# 5V_Block.net
KiCad netlist of a schematic drawn in Altium Designer
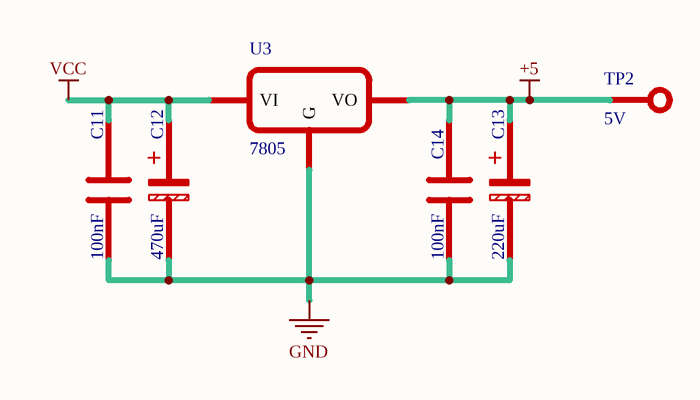
[diagram p0: 5V_Block.SchDoc]

(export (version "E")
  (design (tool "Eeschema 10.0.6"))
  (components
    (comp (ref "C11")
      (value "100nF")
      (footprint "C0805")
      (description "Ceramic Capacitor")
      (libsource (lib "CTAI-Library") (part "CAP-CER"))
    )
    (comp (ref "C12")
      (value "470uF")
      (footprint "CAP-AL-4x5.4")
      (description "Aluminum Capacitor")
      (libsource (lib "CTAI-Library") (part "CAP-ALU"))
    )
    (comp (ref "C13")
      (value "220uF")
      (footprint "CAP-AL-4x5.4")
      (description "Aluminum Capacitor")
      (libsource (lib "CTAI-Library") (part "CAP-ALU"))
    )
    (comp (ref "C14")
      (value "100nF")
      (footprint "C0805")
      (description "Ceramic Capacitor")
      (libsource (lib "CTAI-Library") (part "CAP-CER"))
    )
    (comp (ref "TP2")
      (value "5V")
      (footprint "Test Point")
      (description "Test Point")
      (libsource (lib "CTAI-Library") (part "TestPoint"))
    )
    (comp (ref "U3")
      (value "7805")
      (footprint "TO-252")
      (description "Regulator intergated chip Series (7805-7808-7812-7815-7824)")
      (libsource (lib "CTAI-Library") (part "78xx"))
    )
  )
  (nets
    (net (code "1") (name "+5") (class "Default")
      (node (ref "C13") (pin "1") (pintype "passive"))
      (node (ref "C14") (pin "2") (pintype "passive"))
      (node (ref "TP2") (pin "1") (pinfunction "1_1") (pintype "passive"))
      (node (ref "U3") (pin "3") (pinfunction "VO_3") (pintype "power_in"))
    )
    (net (code "2") (name "GND") (class "Default")
      (node (ref "C11") (pin "1") (pintype "passive"))
      (node (ref "C12") (pin "2") (pintype "passive"))
      (node (ref "C13") (pin "2") (pintype "passive"))
      (node (ref "C14") (pin "1") (pintype "passive"))
      (node (ref "U3") (pin "2") (pinfunction "G_2") (pintype "power_in"))
    )
    (net (code "3") (name "VCC") (class "Default")
      (node (ref "C11") (pin "2") (pintype "passive"))
      (node (ref "C12") (pin "1") (pintype "passive"))
      (node (ref "U3") (pin "1") (pinfunction "VI_1") (pintype "power_in"))
    )
  )
)
